# 15_PM8916_CHARGING_GPIO.net
KiCad netlist of a schematic drawn in Altium Designer
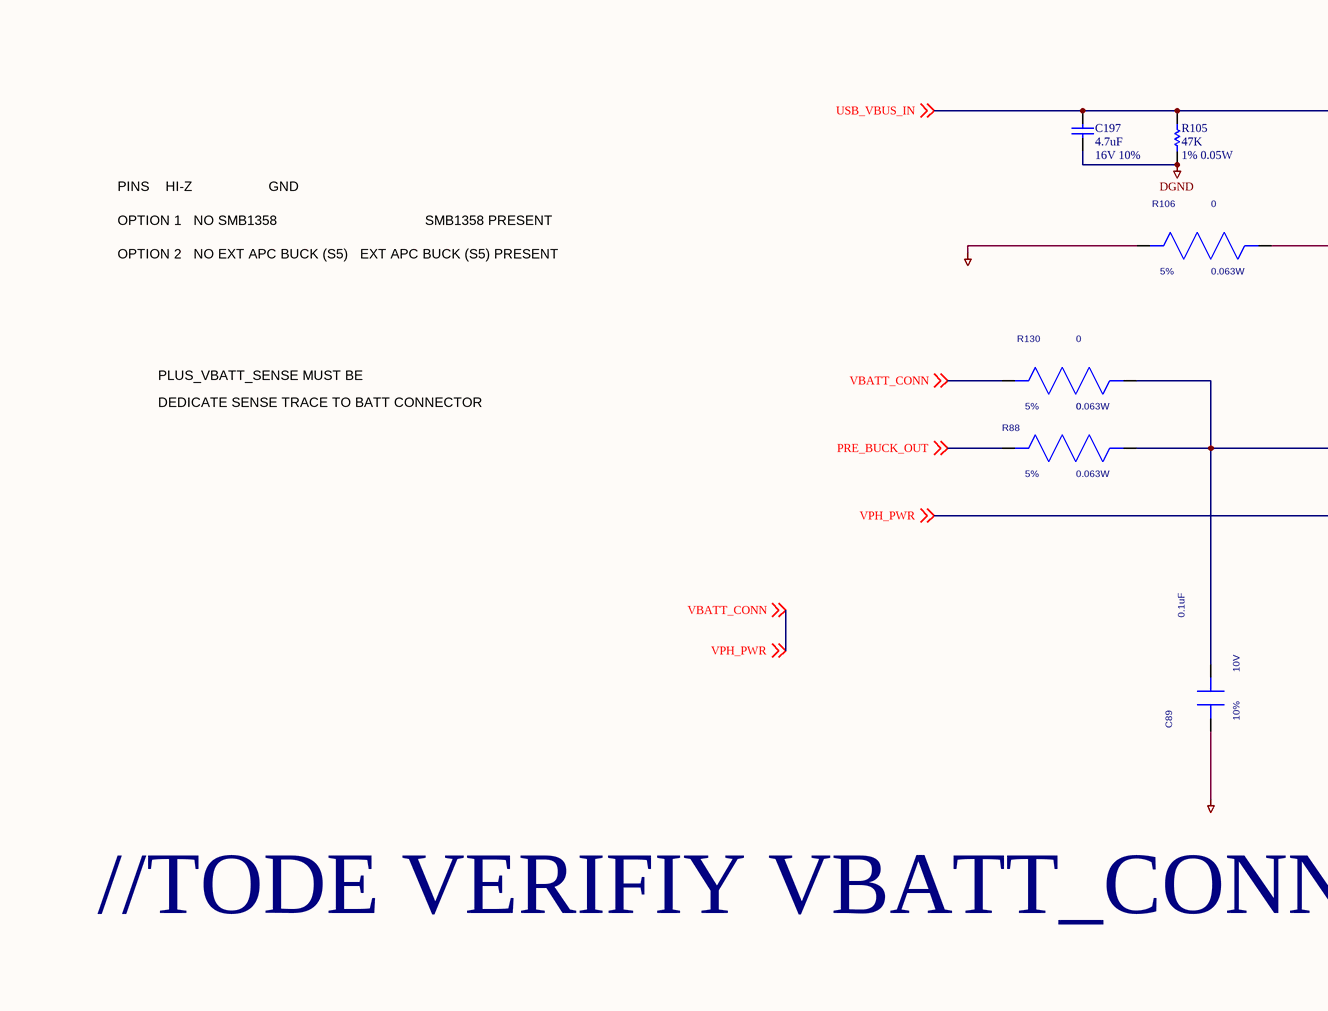
[diagram p0: 15 PM8916_CHARGING GPIO.SchDoc, top left]
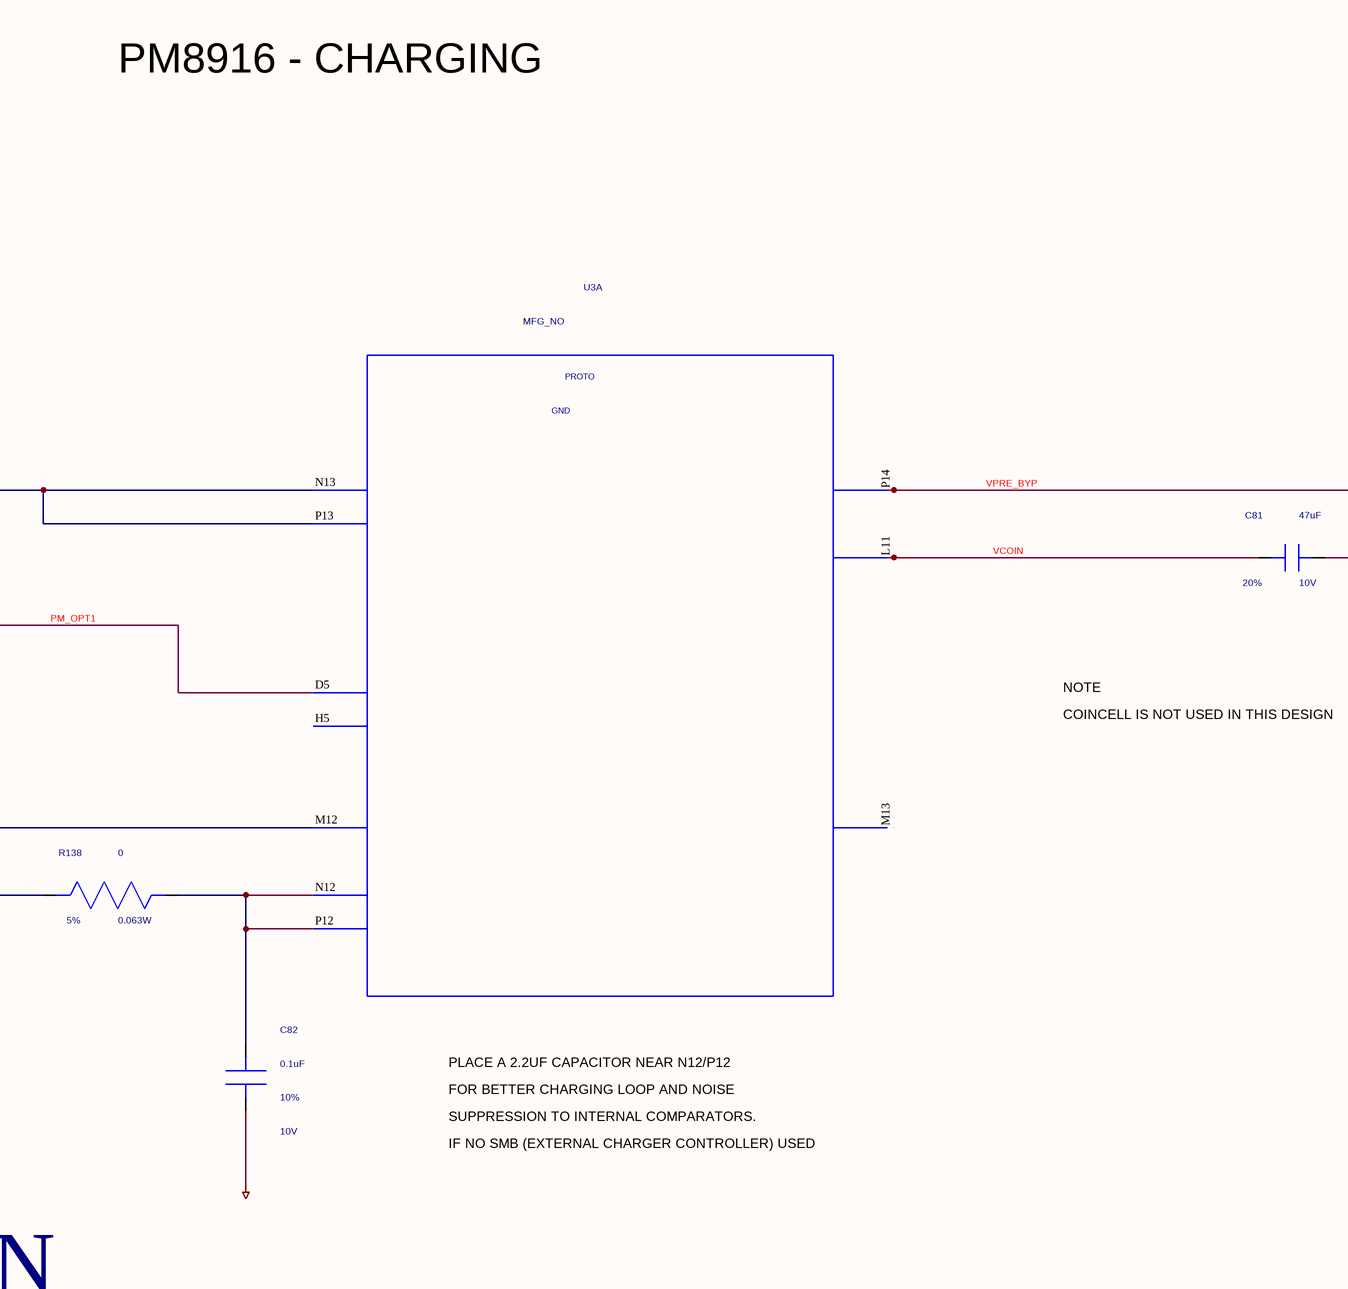
[diagram p1: 15 PM8916_CHARGING GPIO.SchDoc, top middle]
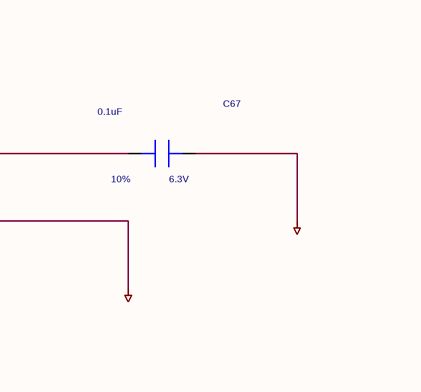
[diagram p2: 15 PM8916_CHARGING GPIO.SchDoc, top right]
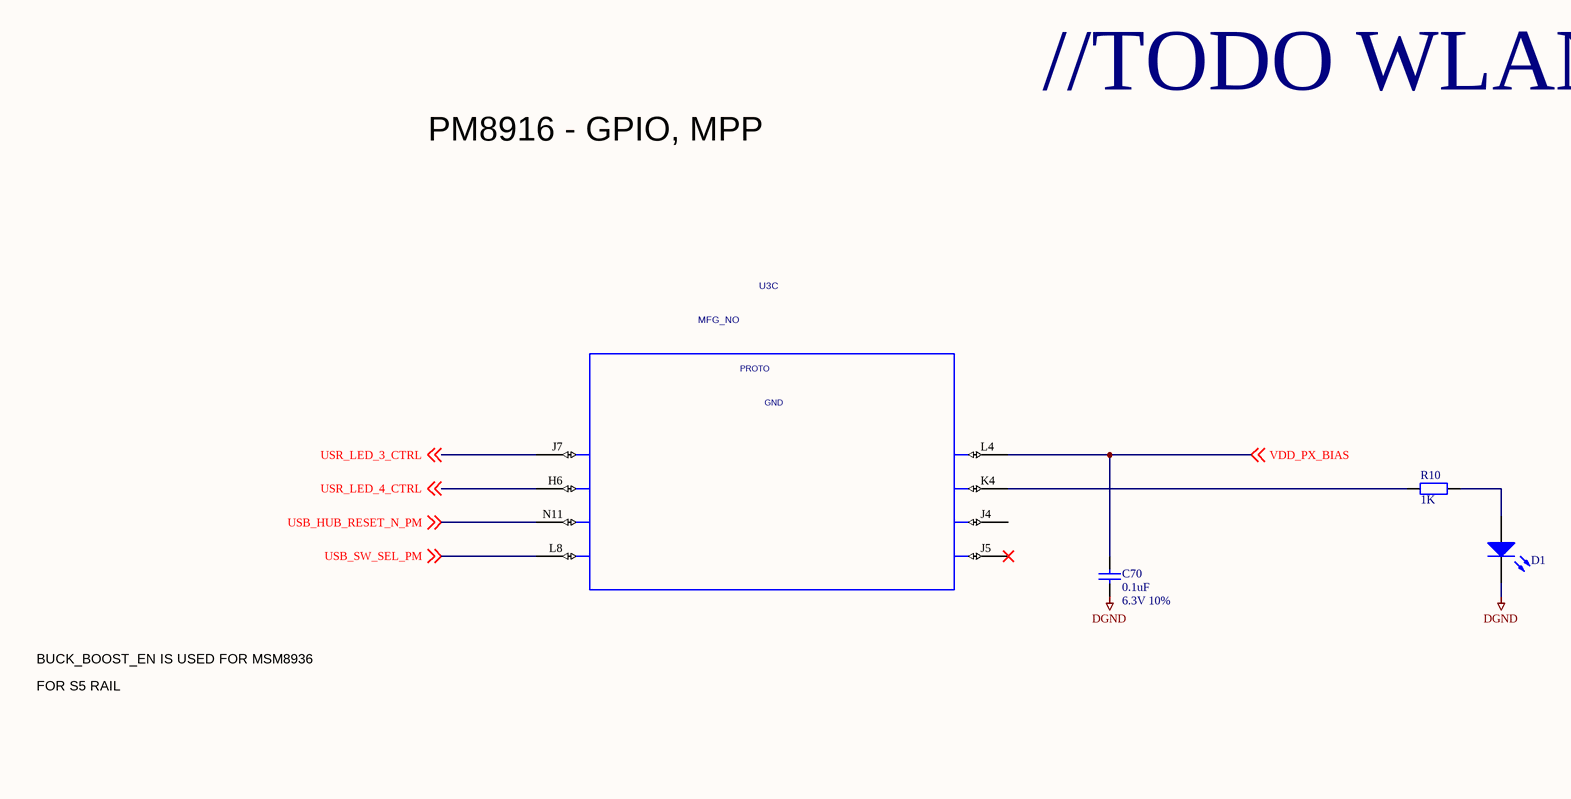
[diagram p3: 15 PM8916_CHARGING GPIO.SchDoc, bottom left]
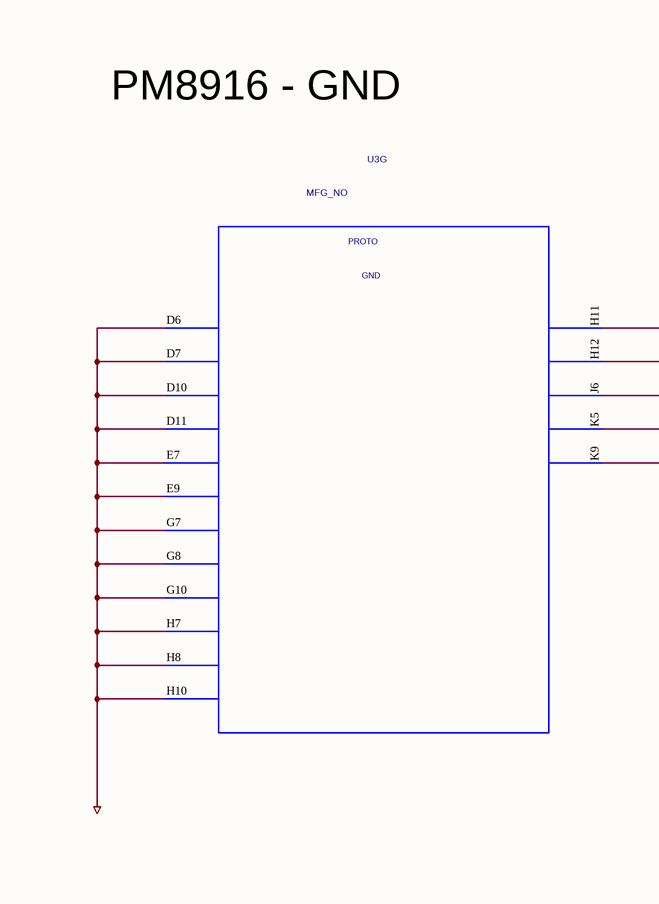
[diagram p4: 15 PM8916_CHARGING GPIO.SchDoc, bottom middle]
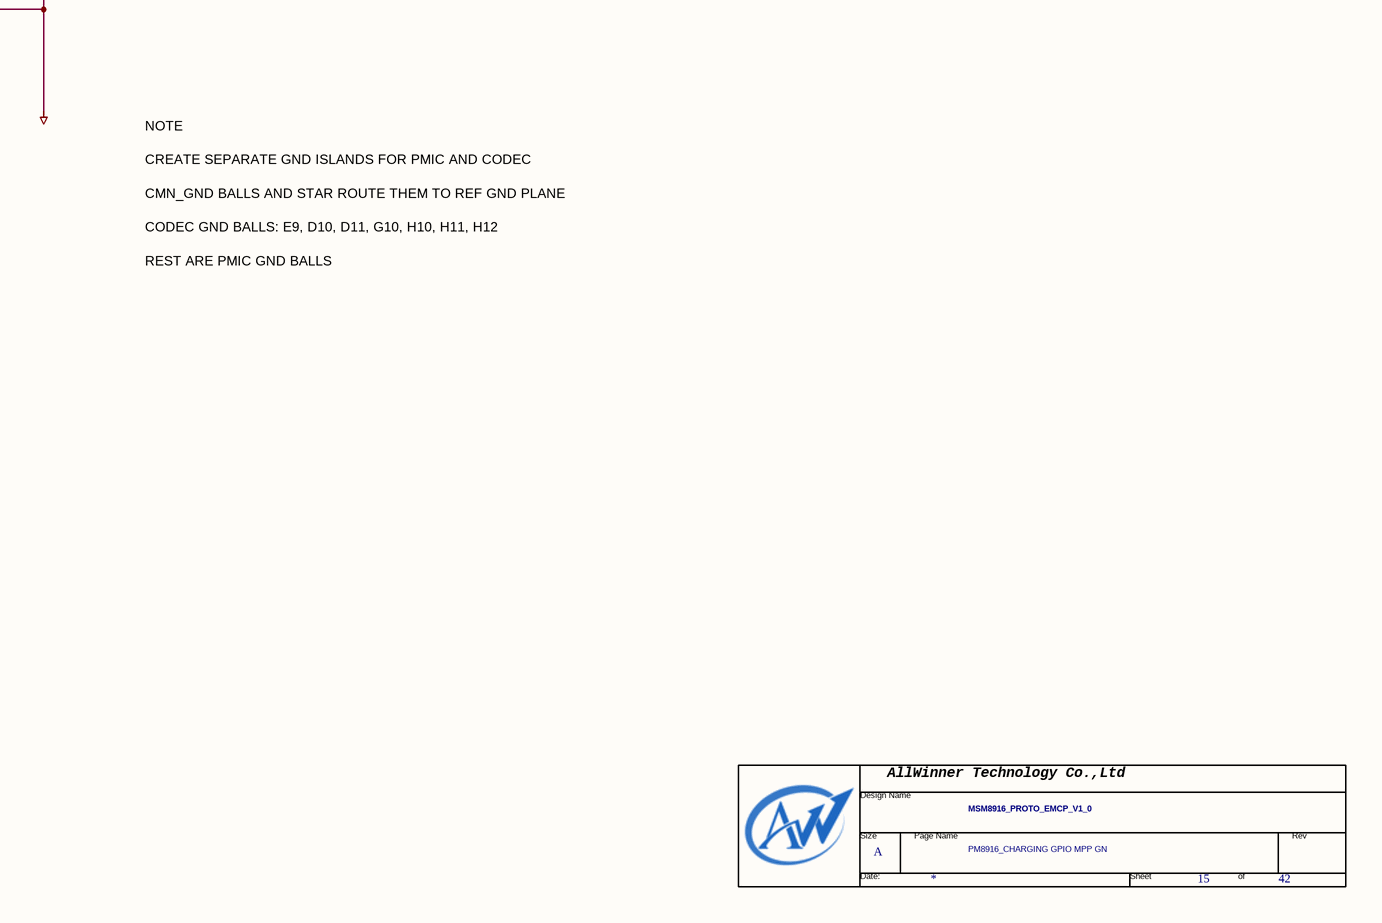
[diagram p5: 15 PM8916_CHARGING GPIO.SchDoc, bottom right]

(export (version "E")
  (design (tool "Eeschema 10.0.6"))
  (components
    (comp (ref "C67")
      (value "0.1uF")
      (footprint "0402C")
      (fields
        (field (name "VOLT") "10%")
        (field (name "TOLERANCE") "6.3V")
        (field (name "PART_NUMBER") "MCN_NO")
      )
      (libsource (lib "MSM8916_DRAM_PMIC_REF_Library") (part "CAP#1"))
    )
    (comp (ref "C70")
      (value "0.1uF")
      (footprint "0402C")
      (description "Capacitor")
      (fields (field (name "ALTIUM_VALUE") "6.3V 10%") (field (name "PUBLISHER") "Altium Limited"))
      (libsource (lib "Miscellaneous Devices") (part "Cap"))
    )
    (comp (ref "C81")
      (value "47uF")
      (footprint "c0402")
      (fields
        (field (name "VOLT") "10V")
        (field (name "TOLERANCE") "20%")
        (field (name "PART_NUMBER") "MCN_NO")
      )
      (libsource (lib "MSM8916_DRAM_PMIC_REF_Library") (part "CAP#1"))
    )
    (comp (ref "C82")
      (value "0.1uF")
      (footprint "0402C")
      (fields
        (field (name "VOLT") "10V")
        (field (name "TOLERANCE") "10%")
        (field (name "PART_NUMBER") "MCN_NO")
      )
      (libsource (lib "MSM8916_DRAM_PMIC_REF_Library") (part "CAP"))
    )
    (comp (ref "C89")
      (value "0.1uF")
      (footprint "0402C")
      (fields
        (field (name "VOLT") "10V")
        (field (name "TOLERANCE") "10%")
        (field (name "PART_NUMBER") "MCN_NO")
      )
      (libsource (lib "MSM8916_DRAM_PMIC_REF_Library") (part "CAP#1"))
    )
    (comp (ref "C197")
      (value "4.7uF")
      (footprint "C0402")
      (description "Capacitor")
      (fields (field (name "ALTIUM_VALUE") "16V 10%") (field (name "PUBLISHER") "Altium Limited"))
      (libsource (lib "Miscellaneous Devices") (part "Cap"))
    )
    (comp (ref "D1")
      (value "LED0")
      (footprint "LED_0805")
      (description "发光二极管")
      (fields (field (name "PUBLISHER") "Altium Limited"))
      (libsource (lib "Fszhang") (part "LED0"))
    )
    (comp (ref "R10")
      (value "1K")
      (footprint "r0402")
      (description "贴片电阻")
      (fields (field (name "Comment") "Res1") (field (name "PUBLISHER") "Altium Limited"))
      (libsource (lib "Fszhang") (part "Res1"))
    )
    (comp (ref "R88")
      (value "0")
      (footprint "c0402")
      (fields
        (field (name "TOLERANCE") "5%")
        (field (name "POWER") "0.063W")
        (field (name "PART_NUMBER") "MCN_NO")
      )
      (libsource (lib "MSM8916_DRAM_PMIC_REF_Library") (part "RESISTOR_Dup3"))
    )
    (comp (ref "R105")
      (value "47K")
      (footprint "r0402")
      (description "Resistor")
      (fields (field (name "ALTIUM_VALUE") "1% 0.05W") (field (name "PUBLISHER") "Altium Limited"))
      (libsource (lib "Miscellaneous Devices") (part "Res1"))
    )
    (comp (ref "R106")
      (value "0")
      (footprint "c0402")
      (fields
        (field (name "TOLERANCE") "5%")
        (field (name "POWER") "0.063W")
        (field (name "PART_NUMBER") "MCN_NO")
      )
      (libsource (lib "MSM8916_DRAM_PMIC_REF_Library") (part "RESISTOR_Dup3"))
    )
    (comp (ref "R130")
      (value "0")
      (footprint "c0402")
      (fields
        (field (name "TOLERANCE") "5%")
        (field (name "POWER") "0.063W")
        (field (name "PART_NUMBER") "MCN_NO")
      )
      (libsource (lib "MSM8916_DRAM_PMIC_REF_Library") (part "RESISTOR_Dup3"))
    )
    (comp (ref "R138")
      (value "0")
      (footprint "c0402")
      (fields
        (field (name "TOLERANCE") "5%")
        (field (name "POWER") "0.063W")
        (field (name "PART_NUMBER") "MCN_NO")
      )
      (libsource (lib "MSM8916_DRAM_PMIC_REF_Library") (part "RESISTOR_Dup3"))
    )
    (comp (ref "U3")
      (value "ASIC_PM8916")
      (footprint "PM-8916-0-176NSP-TR-00-0")
      (fields
        (field (name "SYMNAME") "GND")
        (field (name "PART_NUMBER") "MCN_NO")
        (field (name "PART_ID") "MFG_NO")
        (field (name "BLOCKID") "PROTO")
      )
      (libsource (lib "MSM8916_DRAM_PMIC_REF_Library") (part "ASIC_PM8916"))
    )
  )
  (nets
    (net (code "1") (name "/PM_OPT1") (class "Default")
      (node (ref "R106") (pin "2") (pinfunction "NEG_2") (pintype "bidirectional"))
      (node (ref "U3") (pin "D5") (pinfunction "OPTION1_D5") (pintype "bidirectional"))
    )
    (net (code "2") (name "/VCOIN") (class "Default")
      (node (ref "C81") (pin "1") (pinfunction "POS_1") (pintype "bidirectional"))
      (node (ref "U3") (pin "L11") (pinfunction "VCOIN_L11") (pintype "bidirectional"))
    )
    (net (code "3") (name "/VPRE_BYP") (class "Default")
      (node (ref "C67") (pin "2") (pinfunction "NEG_2") (pintype "bidirectional"))
      (node (ref "U3") (pin "P14") (pinfunction "VPRE_BYP_P14") (pintype "bidirectional"))
    )
    (net (code "4") (name "DGND") (class "Default")
      (node (ref "C197") (pin "1") (pinfunction "1_1") (pintype "passive"))
      (node (ref "C67") (pin "1") (pinfunction "POS_1") (pintype "bidirectional"))
      (node (ref "C70") (pin "1") (pinfunction "1_1") (pintype "passive"))
      (node (ref "C81") (pin "2") (pinfunction "NEG_2") (pintype "bidirectional"))
      (node (ref "C82") (pin "2") (pinfunction "NEG_2") (pintype "bidirectional"))
      (node (ref "C89") (pin "1") (pinfunction "POS_1") (pintype "bidirectional"))
      (node (ref "D1") (pin "2") (pinfunction "K_2") (pintype "passive"))
      (node (ref "R105") (pin "1") (pinfunction "1_1") (pintype "passive"))
      (node (ref "R106") (pin "1") (pinfunction "POS_1") (pintype "bidirectional"))
      (node (ref "U3") (pin "D10") (pinfunction "CMN_GND_3_D10") (pintype "input"))
      (node (ref "U3") (pin "D11") (pinfunction "CMN_GND_4_D11") (pintype "input"))
      (node (ref "U3") (pin "D6") (pinfunction "CMN_GND_1_D6") (pintype "input"))
      (node (ref "U3") (pin "D7") (pinfunction "CMN_GND_2_D7") (pintype "input"))
      (node (ref "U3") (pin "E7") (pinfunction "CMN_GND_5_E7") (pintype "input"))
      (node (ref "U3") (pin "E9") (pinfunction "CMN_GND_6_E9") (pintype "input"))
      (node (ref "U3") (pin "G10") (pinfunction "CMN_GND_9_G10") (pintype "input"))
      (node (ref "U3") (pin "G7") (pinfunction "CMN_GND_7_G7") (pintype "input"))
      (node (ref "U3") (pin "G8") (pinfunction "CMN_GND_8_G8") (pintype "input"))
      (node (ref "U3") (pin "H10") (pinfunction "CMN_GND_12_H10") (pintype "input"))
      (node (ref "U3") (pin "H11") (pinfunction "CMN_GND_13_H11") (pintype "input"))
      (node (ref "U3") (pin "H12") (pinfunction "CMN_GND_14_H12") (pintype "input"))
      (node (ref "U3") (pin "H7") (pinfunction "CMN_GND_10_H7") (pintype "input"))
      (node (ref "U3") (pin "H8") (pinfunction "CMN_GND_11_H8") (pintype "input"))
      (node (ref "U3") (pin "J6") (pinfunction "CMN_GND_15_J6") (pintype "input"))
      (node (ref "U3") (pin "K5") (pinfunction "CMN_GND_16_K5") (pintype "input"))
      (node (ref "U3") (pin "K9") (pinfunction "CMN_GND_17_K9") (pintype "input"))
    )
    (net (code "5") (name "Net-(C82-POS)") (class "Default")
      (node (ref "C82") (pin "1") (pinfunction "POS_1") (pintype "bidirectional"))
      (node (ref "R138") (pin "2") (pinfunction "NEG_2") (pintype "bidirectional"))
      (node (ref "U3") (pin "N12") (pinfunction "VBAT1_N12") (pintype "bidirectional"))
      (node (ref "U3") (pin "P12") (pinfunction "VBAT2_P12") (pintype "bidirectional"))
    )
    (net (code "6") (name "Net-(C89-NEG)") (class "Default")
      (node (ref "C89") (pin "2") (pinfunction "NEG_2") (pintype "bidirectional"))
      (node (ref "R130") (pin "2") (pinfunction "NEG_2") (pintype "bidirectional"))
      (node (ref "R88") (pin "2") (pinfunction "NEG_2") (pintype "bidirectional"))
      (node (ref "U3") (pin "M12") (pinfunction "VBAT_SNS_M12") (pintype "bidirectional"))
    )
    (net (code "7") (name "Net-(D1-A)") (class "Default")
      (node (ref "D1") (pin "1") (pinfunction "A_1") (pintype "passive"))
      (node (ref "R10") (pin "2") (pinfunction "2_2") (pintype "passive"))
    )
    (net (code "8") (name "Net-(U3C-MPP2)") (class "Default")
      (node (ref "R10") (pin "1") (pinfunction "1_1") (pintype "passive"))
      (node (ref "U3") (pin "K4") (pinfunction "MPP2_K4") (pintype "bidirectional"))
    )
    (net (code "9") (name "PRE_BUCK_OUT") (class "Default")
      (node (ref "R88") (pin "1") (pinfunction "POS_1") (pintype "bidirectional"))
    )
    (net (code "10") (name "USB_HUB_RESET_N_PM") (class "Default")
      (node (ref "U3") (pin "N11") (pinfunction "GPIO3_N11") (pintype "bidirectional"))
    )
    (net (code "11") (name "USB_SW_SEL_PM") (class "Default")
      (node (ref "U3") (pin "L8") (pinfunction "GPIO4_L8") (pintype "bidirectional"))
    )
    (net (code "12") (name "USB_VBUS_IN") (class "Default")
      (node (ref "C197") (pin "2") (pinfunction "2_2") (pintype "passive"))
      (node (ref "R105") (pin "2") (pinfunction "2_2") (pintype "passive"))
      (node (ref "U3") (pin "N13") (pinfunction "USB_IN1_N13") (pintype "bidirectional"))
      (node (ref "U3") (pin "P13") (pinfunction "USB_IN2_P13") (pintype "bidirectional"))
    )
    (net (code "13") (name "USR_LED_3_CTRL") (class "Default")
      (node (ref "U3") (pin "J7") (pinfunction "GPIO1_J7") (pintype "bidirectional"))
    )
    (net (code "14") (name "USR_LED_4_CTRL") (class "Default")
      (node (ref "U3") (pin "H6") (pinfunction "GPIO2_H6") (pintype "bidirectional"))
    )
    (net (code "15") (name "VBATT_CONN") (class "Default")
      (node (ref "R130") (pin "1") (pinfunction "POS_1") (pintype "bidirectional"))
      (node (ref "R138") (pin "1") (pinfunction "POS_1") (pintype "bidirectional"))
    )
    (net (code "16") (name "VDD_PX_BIAS") (class "Default")
      (node (ref "C70") (pin "2") (pinfunction "2_2") (pintype "passive"))
      (node (ref "U3") (pin "L4") (pinfunction "MPP1_L4") (pintype "bidirectional"))
    )
    (net (code "17") (name "unconnected-(U3A-CHG_LED_SINK-PadM13)") (class "Default")
      (node (ref "U3") (pin "M13") (pinfunction "CHG_LED_SINK_M13") (pintype "bidirectional"))
    )
    (net (code "18") (name "unconnected-(U3A-OPTION2-PadH5)") (class "Default")
      (node (ref "U3") (pin "H5") (pinfunction "OPTION2_H5") (pintype "bidirectional"))
    )
    (net (code "19") (name "unconnected-(U3C-MPP3-PadJ4)") (class "Default")
      (node (ref "U3") (pin "J4") (pinfunction "MPP3_J4") (pintype "bidirectional"))
    )
    (net (code "20") (name "unconnected-(U3C-MPP4-PadJ5)") (class "Default")
      (node (ref "U3") (pin "J5") (pinfunction "MPP4_J5") (pintype "bidirectional+no_connect"))
    )
  )
)
